# 1A21J11_J2_Rx_Internal_Connection.net
KiCad netlist of a schematic drawn in Altium Designer
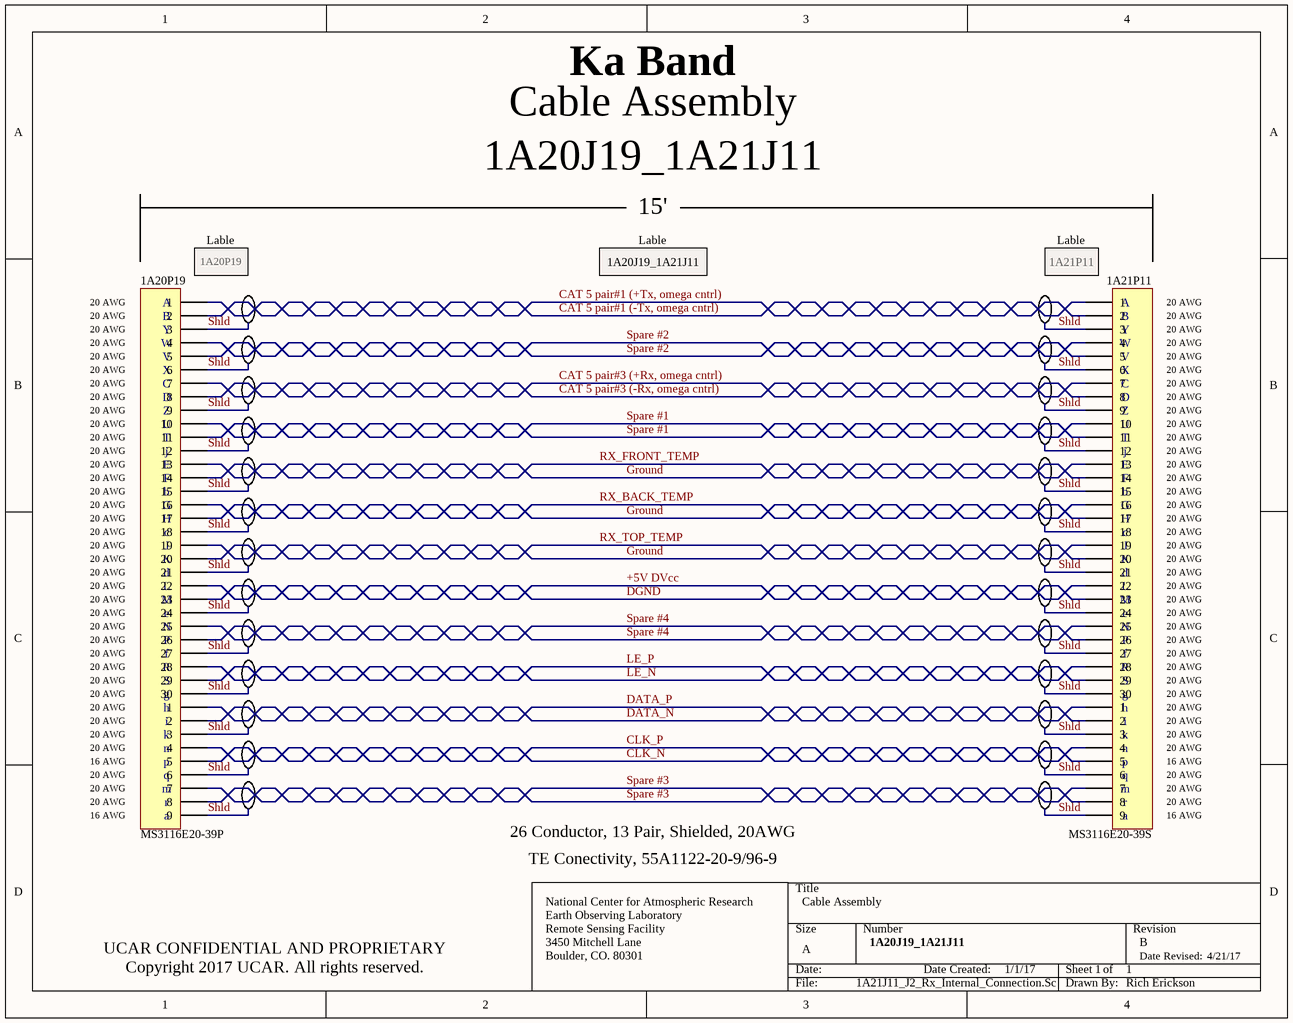
[diagram p0: 1A21J11_J2_Rx_Internal_Connection.SchDoc]

(export (version "E")
  (design (tool "Eeschema 10.0.6"))
  (components
    (comp (ref "1A20P19")
      (value "MS3126E18-32P")
      (footprint "HDR1X30")
      (description "Header, 30-Pin")
      (fields (field (name "PUBLISHER") "Altium Limited"))
      (libsource (lib "Miscellaneous Connectors") (part "Header 30"))
    )
    (comp (ref "1A20P19a")
      (value "MS3116E20-39P")
      (footprint "HDR1X9")
      (description "Header, 9-Pin")
      (fields (field (name "PUBLISHER") "Altium Limited"))
      (libsource (lib "") (part "Header 9_1"))
    )
    (comp (ref "1A21P11")
      (value "MS3126E18-32S")
      (footprint "HDR1X30")
      (description "Header, 30-Pin")
      (fields (field (name "PUBLISHER") "Altium Limited"))
      (libsource (lib "") (part "Header 30_1"))
    )
    (comp (ref "1A21P11a")
      (value "MS3116E20-39S")
      (footprint "HDR1X9")
      (description "Header, 9-Pin")
      (fields (field (name "PUBLISHER") "Altium Limited"))
      (libsource (lib "Miscellaneous Connectors") (part "Header 9"))
    )
  )
  (nets
    (net (code "1") (name "/+5V DVcc") (class "Default")
      (node (ref "1A20P19") (pin "22") (pinfunction "22_22") (pintype "passive"))
      (node (ref "1A21P11") (pin "22") (pinfunction "22_22") (pintype "passive"))
    )
    (net (code "2") (name "/CAT 5 pair#1 (+Tx, omega cntrl)") (class "Default")
      (node (ref "1A20P19") (pin "1") (pinfunction "1_1") (pintype "passive"))
      (node (ref "1A21P11") (pin "1") (pinfunction "1_1") (pintype "passive"))
    )
    (net (code "3") (name "/CAT 5 pair#1 (-Tx, omega cntrl)") (class "Default")
      (node (ref "1A20P19") (pin "2") (pinfunction "2_2") (pintype "passive"))
      (node (ref "1A21P11") (pin "2") (pinfunction "2_2") (pintype "passive"))
    )
    (net (code "4") (name "/CAT 5 pair#3 (+Rx, omega cntrl)") (class "Default")
      (node (ref "1A20P19") (pin "7") (pinfunction "7_7") (pintype "passive"))
      (node (ref "1A21P11") (pin "7") (pinfunction "7_7") (pintype "passive"))
    )
    (net (code "5") (name "/CAT 5 pair#3 (-Rx, omega cntrl)") (class "Default")
      (node (ref "1A20P19") (pin "8") (pinfunction "8_8") (pintype "passive"))
      (node (ref "1A21P11") (pin "8") (pinfunction "8_8") (pintype "passive"))
    )
    (net (code "6") (name "/CLK_N") (class "Default")
      (node (ref "1A20P19a") (pin "5") (pinfunction "5_5") (pintype "passive"))
      (node (ref "1A21P11a") (pin "5") (pinfunction "5_5") (pintype "passive"))
    )
    (net (code "7") (name "/CLK_P") (class "Default")
      (node (ref "1A20P19a") (pin "4") (pinfunction "4_4") (pintype "passive"))
      (node (ref "1A21P11a") (pin "4") (pinfunction "4_4") (pintype "passive"))
    )
    (net (code "8") (name "/DATA_N") (class "Default")
      (node (ref "1A20P19a") (pin "2") (pinfunction "2_2") (pintype "passive"))
      (node (ref "1A21P11a") (pin "2") (pinfunction "2_2") (pintype "passive"))
    )
    (net (code "9") (name "/DATA_P") (class "Default")
      (node (ref "1A20P19a") (pin "1") (pinfunction "1_1") (pintype "passive"))
      (node (ref "1A21P11a") (pin "1") (pinfunction "1_1") (pintype "passive"))
    )
    (net (code "10") (name "/DGND") (class "Default")
      (node (ref "1A20P19") (pin "23") (pinfunction "23_23") (pintype "passive"))
      (node (ref "1A21P11") (pin "23") (pinfunction "23_23") (pintype "passive"))
    )
    (net (code "11") (name "/Ground") (class "Default")
      (node (ref "1A20P19") (pin "14") (pinfunction "14_14") (pintype "passive"))
      (node (ref "1A20P19") (pin "17") (pinfunction "17_17") (pintype "passive"))
      (node (ref "1A20P19") (pin "20") (pinfunction "20_20") (pintype "passive"))
      (node (ref "1A21P11") (pin "14") (pinfunction "14_14") (pintype "passive"))
      (node (ref "1A21P11") (pin "17") (pinfunction "17_17") (pintype "passive"))
      (node (ref "1A21P11") (pin "20") (pinfunction "20_20") (pintype "passive"))
    )
    (net (code "12") (name "/LE_N") (class "Default")
      (node (ref "1A20P19") (pin "29") (pinfunction "29_29") (pintype "passive"))
      (node (ref "1A21P11") (pin "29") (pinfunction "29_29") (pintype "passive"))
    )
    (net (code "13") (name "/LE_P") (class "Default")
      (node (ref "1A20P19") (pin "28") (pinfunction "28_28") (pintype "passive"))
      (node (ref "1A21P11") (pin "28") (pinfunction "28_28") (pintype "passive"))
    )
    (net (code "14") (name "/RX_BACK_TEMP") (class "Default")
      (node (ref "1A20P19") (pin "16") (pinfunction "16_16") (pintype "passive"))
      (node (ref "1A21P11") (pin "16") (pinfunction "16_16") (pintype "passive"))
    )
    (net (code "15") (name "/RX_FRONT_TEMP") (class "Default")
      (node (ref "1A20P19") (pin "13") (pinfunction "13_13") (pintype "passive"))
      (node (ref "1A21P11") (pin "13") (pinfunction "13_13") (pintype "passive"))
    )
    (net (code "16") (name "/RX_TOP_TEMP") (class "Default")
      (node (ref "1A20P19") (pin "19") (pinfunction "19_19") (pintype "passive"))
      (node (ref "1A21P11") (pin "19") (pinfunction "19_19") (pintype "passive"))
    )
    (net (code "17") (name "/Shld") (class "Default")
      (node (ref "1A20P19") (pin "12") (pinfunction "12_12") (pintype "passive"))
      (node (ref "1A20P19") (pin "15") (pinfunction "15_15") (pintype "passive"))
      (node (ref "1A20P19") (pin "18") (pinfunction "18_18") (pintype "passive"))
      (node (ref "1A20P19") (pin "21") (pinfunction "21_21") (pintype "passive"))
      (node (ref "1A20P19") (pin "24") (pinfunction "24_24") (pintype "passive"))
      (node (ref "1A20P19") (pin "27") (pinfunction "27_27") (pintype "passive"))
      (node (ref "1A20P19") (pin "3") (pinfunction "3_3") (pintype "passive"))
      (node (ref "1A20P19") (pin "30") (pinfunction "30_30") (pintype "passive"))
      (node (ref "1A20P19") (pin "6") (pinfunction "6_6") (pintype "passive"))
      (node (ref "1A20P19") (pin "9") (pinfunction "9_9") (pintype "passive"))
      (node (ref "1A20P19a") (pin "3") (pinfunction "3_3") (pintype "passive"))
      (node (ref "1A20P19a") (pin "6") (pinfunction "6_6") (pintype "passive"))
      (node (ref "1A20P19a") (pin "9") (pinfunction "9_9") (pintype "passive"))
      (node (ref "1A21P11") (pin "12") (pinfunction "12_12") (pintype "passive"))
      (node (ref "1A21P11") (pin "15") (pinfunction "15_15") (pintype "passive"))
      (node (ref "1A21P11") (pin "18") (pinfunction "18_18") (pintype "passive"))
      (node (ref "1A21P11") (pin "21") (pinfunction "21_21") (pintype "passive"))
      (node (ref "1A21P11") (pin "24") (pinfunction "24_24") (pintype "passive"))
      (node (ref "1A21P11") (pin "27") (pinfunction "27_27") (pintype "passive"))
      (node (ref "1A21P11") (pin "3") (pinfunction "3_3") (pintype "passive"))
      (node (ref "1A21P11") (pin "30") (pinfunction "30_30") (pintype "passive"))
      (node (ref "1A21P11") (pin "6") (pinfunction "6_6") (pintype "passive"))
      (node (ref "1A21P11") (pin "9") (pinfunction "9_9") (pintype "passive"))
      (node (ref "1A21P11a") (pin "3") (pinfunction "3_3") (pintype "passive"))
      (node (ref "1A21P11a") (pin "6") (pinfunction "6_6") (pintype "passive"))
      (node (ref "1A21P11a") (pin "9") (pinfunction "9_9") (pintype "passive"))
    )
    (net (code "18") (name "/Spare #1") (class "Default")
      (node (ref "1A20P19") (pin "10") (pinfunction "10_10") (pintype "passive"))
      (node (ref "1A20P19") (pin "11") (pinfunction "11_11") (pintype "passive"))
      (node (ref "1A21P11") (pin "10") (pinfunction "10_10") (pintype "passive"))
      (node (ref "1A21P11") (pin "11") (pinfunction "11_11") (pintype "passive"))
    )
    (net (code "19") (name "/Spare #2") (class "Default")
      (node (ref "1A20P19") (pin "4") (pinfunction "4_4") (pintype "passive"))
      (node (ref "1A20P19") (pin "5") (pinfunction "5_5") (pintype "passive"))
      (node (ref "1A21P11") (pin "4") (pinfunction "4_4") (pintype "passive"))
      (node (ref "1A21P11") (pin "5") (pinfunction "5_5") (pintype "passive"))
    )
    (net (code "20") (name "/Spare #3") (class "Default")
      (node (ref "1A20P19a") (pin "7") (pinfunction "7_7") (pintype "passive"))
      (node (ref "1A20P19a") (pin "8") (pinfunction "8_8") (pintype "passive"))
      (node (ref "1A21P11a") (pin "7") (pinfunction "7_7") (pintype "passive"))
      (node (ref "1A21P11a") (pin "8") (pinfunction "8_8") (pintype "passive"))
    )
    (net (code "21") (name "/Spare #4") (class "Default")
      (node (ref "1A20P19") (pin "25") (pinfunction "25_25") (pintype "passive"))
      (node (ref "1A20P19") (pin "26") (pinfunction "26_26") (pintype "passive"))
      (node (ref "1A21P11") (pin "25") (pinfunction "25_25") (pintype "passive"))
      (node (ref "1A21P11") (pin "26") (pinfunction "26_26") (pintype "passive"))
    )
  )
)
